# v1.net
KiCad netlist of a schematic drawn in EAGLE
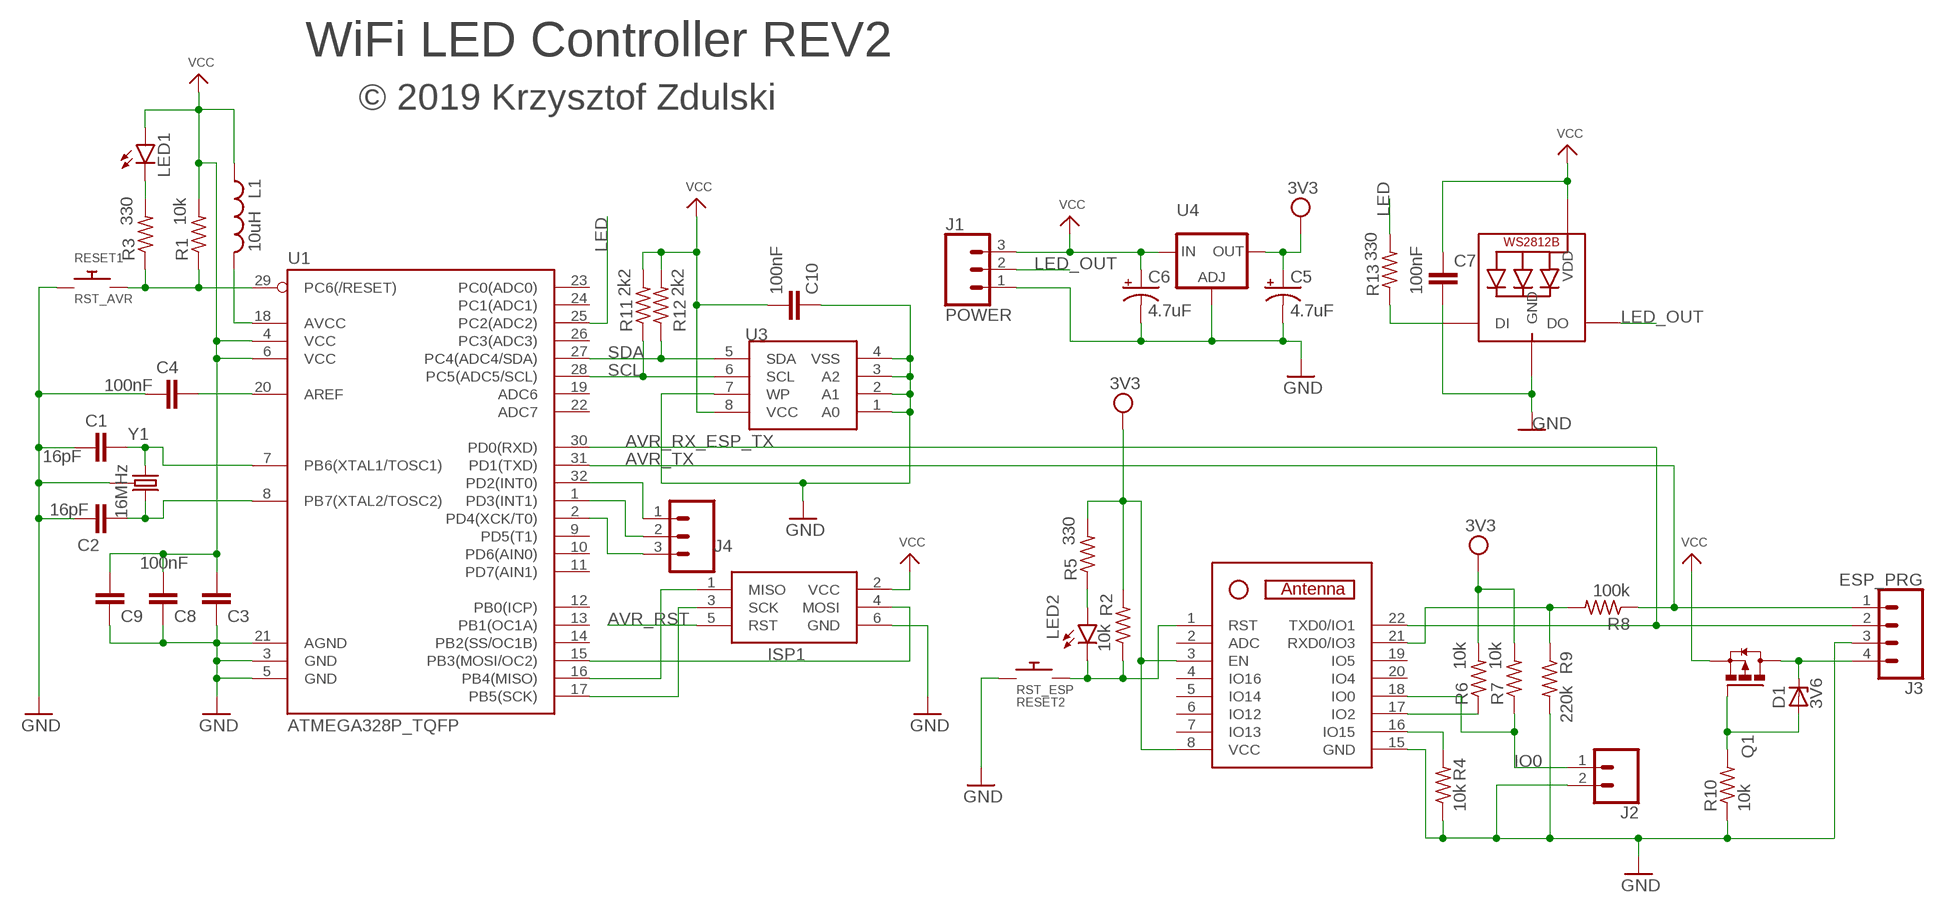
[diagram p0: schematic, sheet 1]

(export (version "E")
  (design (tool "Eeschema 10.0.6"))
  (components
    (comp (ref "C1")
      (value "16pF")
      (footprint "eagle-import:C0603K")
      (libsource (lib "eagle-import") (part "C-EUC0603K"))
    )
    (comp (ref "C2")
      (value "16pF")
      (footprint "eagle-import:C0603K")
      (libsource (lib "eagle-import") (part "C-EUC0603K"))
    )
    (comp (ref "C3")
      (value "100nF")
      (footprint "eagle-import:C0603")
      (libsource (lib "eagle-import") (part "C-EUC0603"))
    )
    (comp (ref "C4")
      (value "100nF")
      (footprint "eagle-import:C0603")
      (libsource (lib "eagle-import") (part "C-EUC0603"))
    )
    (comp (ref "C5")
      (value "4.7uF")
      (footprint "eagle-import:153CLV-0405")
      (libsource (lib "eagle-import") (part "CPOL-US153CLV-0405"))
    )
    (comp (ref "C6")
      (value "4.7uF")
      (footprint "eagle-import:153CLV-0405")
      (libsource (lib "eagle-import") (part "CPOL-US153CLV-0405"))
    )
    (comp (ref "C7")
      (value "100nF")
      (footprint "eagle-import:C0603")
      (libsource (lib "eagle-import") (part "C-EUC0603"))
    )
    (comp (ref "C8")
      (value "100nF")
      (footprint "eagle-import:C0603")
      (libsource (lib "eagle-import") (part "C-EUC0603"))
    )
    (comp (ref "C9")
      (value "100nF")
      (footprint "eagle-import:C0603")
      (libsource (lib "eagle-import") (part "C-EUC0603"))
    )
    (comp (ref "C10")
      (value "100nF")
      (footprint "eagle-import:C0603")
      (libsource (lib "eagle-import") (part "C-EUC0603"))
    )
    (comp (ref "D1")
      (value "3V6")
      (footprint "eagle-import:SOD123")
      (libsource (lib "eagle-import") (part "ZENNER_DIODE"))
    )
    (comp (ref "D2")
      (value "WS2812B")
      (footprint "eagle-import:WS2812B")
      (libsource (lib "eagle-import") (part "WS2812B"))
    )
    (comp (ref "ISP1")
      (value "AVRISP-6")
      (footprint "eagle-import:AVRISP")
      (libsource (lib "eagle-import") (part "AVRISP-6"))
    )
    (comp (ref "J1")
      (value "POWER")
      (footprint "eagle-import:MX-22-05-3031")
      (libsource (lib "eagle-import") (part "MX-22-05-3031"))
    )
    (comp (ref "J2")
      (value "CONN_02")
      (footprint "eagle-import:1X02")
      (libsource (lib "eagle-import") (part "CONN_02"))
    )
    (comp (ref "J3")
      (value "ESP_PRG")
      (footprint "eagle-import:1X04")
      (libsource (lib "eagle-import") (part "CONN_04"))
    )
    (comp (ref "J4")
      (value "CONN_03")
      (footprint "eagle-import:1X03")
      (libsource (lib "eagle-import") (part "CONN_03"))
    )
    (comp (ref "L1")
      (value "10uH")
      (footprint "eagle-import:L2012C")
      (libsource (lib "eagle-import") (part "L-USL2012C"))
    )
    (comp (ref "LED1")
      (value "LEDCHIP-LED0603")
      (footprint "eagle-import:CHIP-LED0603")
      (libsource (lib "eagle-import") (part "LEDCHIP-LED0603"))
    )
    (comp (ref "LED2")
      (value "LEDCHIP-LED0603")
      (footprint "eagle-import:CHIP-LED0603")
      (libsource (lib "eagle-import") (part "LEDCHIP-LED0603"))
    )
    (comp (ref "Q1")
      (value "FDN360P")
      (footprint "eagle-import:SUPER-SOT3")
      (libsource (lib "eagle-import") (part "FDN360P"))
    )
    (comp (ref "R1")
      (value "10k")
      (footprint "eagle-import:R0402")
      (libsource (lib "eagle-import") (part "R-US_R0402"))
    )
    (comp (ref "R2")
      (value "10k")
      (footprint "eagle-import:R0402")
      (libsource (lib "eagle-import") (part "R-US_R0402"))
    )
    (comp (ref "R3")
      (value "330")
      (footprint "eagle-import:R0603")
      (libsource (lib "eagle-import") (part "R-US_R0603"))
    )
    (comp (ref "R4")
      (value "10k")
      (footprint "eagle-import:R0603")
      (libsource (lib "eagle-import") (part "R-US_R0603"))
    )
    (comp (ref "R5")
      (value "330")
      (footprint "eagle-import:R0603")
      (libsource (lib "eagle-import") (part "R-US_R0603"))
    )
    (comp (ref "R6")
      (value "10k")
      (footprint "eagle-import:R0603")
      (libsource (lib "eagle-import") (part "R-US_R0603"))
    )
    (comp (ref "R7")
      (value "10k")
      (footprint "eagle-import:R0603")
      (libsource (lib "eagle-import") (part "R-US_R0603"))
    )
    (comp (ref "R8")
      (value "100k")
      (footprint "eagle-import:R0603")
      (libsource (lib "eagle-import") (part "R-US_R0603"))
    )
    (comp (ref "R9")
      (value "220k")
      (footprint "eagle-import:R0603")
      (libsource (lib "eagle-import") (part "R-US_R0603"))
    )
    (comp (ref "R10")
      (value "10k")
      (footprint "eagle-import:R0402")
      (libsource (lib "eagle-import") (part "R-US_R0402"))
    )
    (comp (ref "R11")
      (value "2k2")
      (footprint "eagle-import:R0603")
      (libsource (lib "eagle-import") (part "R-US_R0603"))
    )
    (comp (ref "R12")
      (value "2k2")
      (footprint "eagle-import:R0603")
      (libsource (lib "eagle-import") (part "R-US_R0603"))
    )
    (comp (ref "R13")
      (value "330")
      (footprint "eagle-import:R0603")
      (libsource (lib "eagle-import") (part "R-US_R0603"))
    )
    (comp (ref "RESET1")
      (value "RST_AVR")
      (footprint "eagle-import:TACTILE_SWITCH_SMD_6.2MM_TALL")
      (libsource (lib "eagle-import") (part "BUTTON"))
    )
    (comp (ref "RESET2")
      (value "RST_ESP")
      (footprint "eagle-import:TACTILE_SWITCH_SMD_6.2MM_TALL")
      (libsource (lib "eagle-import") (part "BUTTON"))
    )
    (comp (ref "U1")
      (value "ATMEGA328P_TQFP")
      (footprint "eagle-import:TQFP32-08")
      (libsource (lib "eagle-import") (part "ATMEGA328P_TQFP"))
    )
    (comp (ref "U2")
      (value "ESP-07")
      (footprint "eagle-import:ESP-07")
      (libsource (lib "eagle-import") (part "ESP-07"))
    )
    (comp (ref "U3")
      (value "EEPROM-I2CTSSOP8")
      (footprint "eagle-import:TSSOP8")
      (libsource (lib "eagle-import") (part "EEPROM-I2CTSSOP8"))
    )
    (comp (ref "U4")
      (value "LD117AS12TR")
      (footprint "eagle-import:SOT223")
      (libsource (lib "eagle-import") (part "LD117A?S12TR"))
    )
    (comp (ref "Y1")
      (value "16MHz")
      (footprint "eagle-import:CRYSTAL-SMD-3.2X2.5MM")
      (libsource (lib "eagle-import") (part "CRYSTAL"))
    )
  )
  (nets
    (net (code "1") (name "/AVR_RST") (class "Default")
      (node (ref "ISP1") (pin "5") (pinfunction "RST_5") (pintype "output"))
      (node (ref "R1") (pin "1") (pinfunction "1_1") (pintype "passive"))
      (node (ref "R3") (pin "1") (pinfunction "1_1") (pintype "passive"))
      (node (ref "RESET1") (pin "B1") (pinfunction "P$2_B1") (pintype "passive"))
      (node (ref "RESET1") (pin "B2") (pinfunction "P$2_B2") (pintype "passive"))
      (node (ref "U1") (pin "29") (pinfunction "PC6(/RESET)_29") (pintype "bidirectional"))
    )
    (net (code "2") (name "/AVR_RX_ESP_TX") (class "Default")
      (node (ref "J3") (pin "2") (pinfunction "2_2") (pintype "passive"))
      (node (ref "U1") (pin "30") (pinfunction "PD0(RXD)_30") (pintype "bidirectional"))
      (node (ref "U2") (pin "22") (pinfunction "TXD0/IO1_22") (pintype "bidirectional"))
    )
    (net (code "3") (name "/AVR_TX") (class "Default")
      (node (ref "J3") (pin "1") (pinfunction "1_1") (pintype "passive"))
      (node (ref "R8") (pin "1") (pinfunction "1_1") (pintype "passive"))
      (node (ref "U1") (pin "31") (pinfunction "PD1(TXD)_31") (pintype "bidirectional"))
    )
    (net (code "4") (name "/IO0") (class "Default")
      (node (ref "J2") (pin "1") (pinfunction "1_1") (pintype "passive"))
      (node (ref "R7") (pin "1") (pinfunction "1_1") (pintype "passive"))
      (node (ref "U2") (pin "18") (pinfunction "IO0_18") (pintype "bidirectional"))
    )
    (net (code "5") (name "/LED") (class "Default")
      (node (ref "R13") (pin "2") (pinfunction "2_2") (pintype "passive"))
      (node (ref "U1") (pin "25") (pinfunction "PC2(ADC2)_25") (pintype "bidirectional"))
    )
    (net (code "6") (name "/LED_OUT") (class "Default")
      (node (ref "D2") (pin "2-DOUT") (pinfunction "DO_2-DOUT") (pintype "output"))
      (node (ref "J1") (pin "2") (pinfunction "2_2") (pintype "passive"))
    )
    (net (code "7") (name "/SCL") (class "Default")
      (node (ref "R11") (pin "1") (pinfunction "1_1") (pintype "passive"))
      (node (ref "U1") (pin "28") (pinfunction "PC5(ADC5/SCL)_28") (pintype "bidirectional"))
      (node (ref "U3") (pin "6") (pinfunction "SCL_6") (pintype "bidirectional"))
    )
    (net (code "8") (name "/SDA") (class "Default")
      (node (ref "R12") (pin "1") (pinfunction "1_1") (pintype "passive"))
      (node (ref "U1") (pin "27") (pinfunction "PC4(ADC4/SDA)_27") (pintype "bidirectional"))
      (node (ref "U3") (pin "5") (pinfunction "SDA_5") (pintype "bidirectional"))
    )
    (net (code "9") (name "3V3") (class "Default")
      (node (ref "C5") (pin "+") (pinfunction "+_+") (pintype "passive"))
      (node (ref "R2") (pin "2") (pinfunction "2_2") (pintype "passive"))
      (node (ref "R5") (pin "2") (pinfunction "2_2") (pintype "passive"))
      (node (ref "R6") (pin "2") (pinfunction "2_2") (pintype "passive"))
      (node (ref "R7") (pin "2") (pinfunction "2_2") (pintype "passive"))
      (node (ref "U2") (pin "3") (pinfunction "EN_3") (pintype "bidirectional"))
      (node (ref "U2") (pin "8") (pinfunction "VCC_8") (pintype "bidirectional"))
      (node (ref "U4") (pin "4") (pinfunction "OUT_4") (pintype "passive"))
    )
    (net (code "10") (name "GND") (class "Default")
      (node (ref "C1") (pin "2") (pinfunction "2_2") (pintype "passive"))
      (node (ref "C10") (pin "2") (pinfunction "2_2") (pintype "passive"))
      (node (ref "C2") (pin "2") (pinfunction "2_2") (pintype "passive"))
      (node (ref "C3") (pin "2") (pinfunction "2_2") (pintype "passive"))
      (node (ref "C4") (pin "1") (pinfunction "1_1") (pintype "passive"))
      (node (ref "C5") (pin "-") (pinfunction "-_-") (pintype "passive"))
      (node (ref "C6") (pin "-") (pinfunction "-_-") (pintype "passive"))
      (node (ref "C7") (pin "2") (pinfunction "2_2") (pintype "passive"))
      (node (ref "C8") (pin "2") (pinfunction "2_2") (pintype "passive"))
      (node (ref "C9") (pin "2") (pinfunction "2_2") (pintype "passive"))
      (node (ref "D2") (pin "3-GND") (pinfunction "GND_3-GND") (pintype "power_in"))
      (node (ref "ISP1") (pin "6") (pinfunction "GND_6") (pintype "power_in"))
      (node (ref "J1") (pin "1") (pinfunction "1_1") (pintype "passive"))
      (node (ref "J2") (pin "2") (pinfunction "2_2") (pintype "passive"))
      (node (ref "J3") (pin "3") (pinfunction "3_3") (pintype "passive"))
      (node (ref "R10") (pin "1") (pinfunction "1_1") (pintype "passive"))
      (node (ref "R4") (pin "1") (pinfunction "1_1") (pintype "passive"))
      (node (ref "R9") (pin "2") (pinfunction "2_2") (pintype "passive"))
      (node (ref "RESET1") (pin "A1") (pinfunction "P$1_A1") (pintype "passive"))
      (node (ref "RESET1") (pin "A2") (pinfunction "P$1_A2") (pintype "passive"))
      (node (ref "RESET2") (pin "A1") (pinfunction "P$1_A1") (pintype "passive"))
      (node (ref "RESET2") (pin "A2") (pinfunction "P$1_A2") (pintype "passive"))
      (node (ref "U1") (pin "21") (pinfunction "AGND_21") (pintype "bidirectional"))
      (node (ref "U1") (pin "3") (pinfunction "GND_3") (pintype "bidirectional"))
      (node (ref "U1") (pin "5") (pinfunction "GND_5") (pintype "bidirectional"))
      (node (ref "U2") (pin "15") (pinfunction "GND_15") (pintype "bidirectional"))
      (node (ref "U3") (pin "1") (pinfunction "A0_1") (pintype "bidirectional"))
      (node (ref "U3") (pin "2") (pinfunction "A1_2") (pintype "bidirectional"))
      (node (ref "U3") (pin "3") (pinfunction "A2_3") (pintype "bidirectional"))
      (node (ref "U3") (pin "4") (pinfunction "VSS_4") (pintype "power_in"))
      (node (ref "U3") (pin "7") (pinfunction "WP_7") (pintype "bidirectional"))
      (node (ref "U4") (pin "1") (pinfunction "ADJ_1") (pintype "input"))
      (node (ref "Y1") (pin "2") (pinfunction "3_2") (pintype "passive"))
      (node (ref "Y1") (pin "4") (pinfunction "3_4") (pintype "passive"))
    )
    (net (code "11") (name "Net-(D2-DI)") (class "Default")
      (node (ref "D2") (pin "4-DIN") (pinfunction "DI_4-DIN") (pintype "input"))
      (node (ref "R13") (pin "1") (pinfunction "1_1") (pintype "passive"))
    )
    (net (code "12") (name "Net-(ISP1-MISO)") (class "Default")
      (node (ref "ISP1") (pin "1") (pinfunction "MISO_1") (pintype "input"))
      (node (ref "U1") (pin "16") (pinfunction "PB4(MISO)_16") (pintype "bidirectional"))
    )
    (net (code "13") (name "Net-(ISP1-MOSI)") (class "Default")
      (node (ref "ISP1") (pin "4") (pinfunction "MOSI_4") (pintype "output"))
      (node (ref "U1") (pin "15") (pinfunction "PB3(MOSI/OC2)_15") (pintype "bidirectional"))
    )
    (net (code "14") (name "Net-(ISP1-SCK)") (class "Default")
      (node (ref "ISP1") (pin "3") (pinfunction "SCK_3") (pintype "output"))
      (node (ref "U1") (pin "17") (pinfunction "PB5(SCK)_17") (pintype "bidirectional"))
    )
    (net (code "15") (name "Net-(LED1-PadC)") (class "Default")
      (node (ref "LED1") (pin "C") (pinfunction "C_C") (pintype "passive"))
      (node (ref "R3") (pin "2") (pinfunction "2_2") (pintype "passive"))
    )
    (net (code "16") (name "Net-(LED2-PadA)") (class "Default")
      (node (ref "LED2") (pin "A") (pinfunction "A_A") (pintype "passive"))
      (node (ref "R5") (pin "1") (pinfunction "1_1") (pintype "passive"))
    )
    (net (code "17") (name "Net-(Q1-D)") (class "Default")
      (node (ref "D1") (pin "C") (pinfunction "C_C") (pintype "passive"))
      (node (ref "J3") (pin "4") (pinfunction "4_4") (pintype "passive"))
      (node (ref "Q1") (pin "3") (pinfunction "D_3") (pintype "passive"))
    )
    (net (code "18") (name "Net-(Q1-G)") (class "Default")
      (node (ref "D1") (pin "A") (pinfunction "A_A") (pintype "passive"))
      (node (ref "Q1") (pin "1") (pinfunction "G_1") (pintype "passive"))
      (node (ref "R10") (pin "2") (pinfunction "2_2") (pintype "passive"))
    )
    (net (code "19") (name "Net-(U1-AREF)") (class "Default")
      (node (ref "C4") (pin "2") (pinfunction "2_2") (pintype "passive"))
      (node (ref "U1") (pin "20") (pinfunction "AREF_20") (pintype "bidirectional"))
    )
    (net (code "20") (name "Net-(U1-AVCC)") (class "Default")
      (node (ref "L1") (pin "2") (pinfunction "2_2") (pintype "passive"))
      (node (ref "U1") (pin "18") (pinfunction "AVCC_18") (pintype "bidirectional"))
    )
    (net (code "21") (name "Net-(U1-PB6(XTAL1{slash}TOSC1))") (class "Default")
      (node (ref "C1") (pin "1") (pinfunction "1_1") (pintype "passive"))
      (node (ref "U1") (pin "7") (pinfunction "PB6(XTAL1/TOSC1)_7") (pintype "bidirectional"))
      (node (ref "Y1") (pin "1") (pinfunction "1_1") (pintype "passive"))
    )
    (net (code "22") (name "Net-(U1-PB7(XTAL2{slash}TOSC2))") (class "Default")
      (node (ref "C2") (pin "1") (pinfunction "1_1") (pintype "passive"))
      (node (ref "U1") (pin "8") (pinfunction "PB7(XTAL2/TOSC2)_8") (pintype "bidirectional"))
      (node (ref "Y1") (pin "3") (pinfunction "2_3") (pintype "passive"))
    )
    (net (code "23") (name "Net-(U1-PD2(INT0))") (class "Default")
      (node (ref "J4") (pin "1") (pinfunction "1_1") (pintype "passive"))
      (node (ref "U1") (pin "32") (pinfunction "PD2(INT0)_32") (pintype "bidirectional"))
    )
    (net (code "24") (name "Net-(U1-PD3(INT1))") (class "Default")
      (node (ref "J4") (pin "2") (pinfunction "2_2") (pintype "passive"))
      (node (ref "U1") (pin "1") (pinfunction "PD3(INT1)_1") (pintype "bidirectional"))
    )
    (net (code "25") (name "Net-(U1-PD4(XCK{slash}T0))") (class "Default")
      (node (ref "J4") (pin "3") (pinfunction "3_3") (pintype "passive"))
      (node (ref "U1") (pin "2") (pinfunction "PD4(XCK/T0)_2") (pintype "bidirectional"))
    )
    (net (code "26") (name "Net-(U2-IO2)") (class "Default")
      (node (ref "R6") (pin "1") (pinfunction "1_1") (pintype "passive"))
      (node (ref "U2") (pin "17") (pinfunction "IO2_17") (pintype "bidirectional"))
    )
    (net (code "27") (name "Net-(U2-IO15)") (class "Default")
      (node (ref "R4") (pin "2") (pinfunction "2_2") (pintype "passive"))
      (node (ref "U2") (pin "16") (pinfunction "IO15_16") (pintype "bidirectional"))
    )
    (net (code "28") (name "Net-(U2-RST)") (class "Default")
      (node (ref "LED2") (pin "C") (pinfunction "C_C") (pintype "passive"))
      (node (ref "R2") (pin "1") (pinfunction "1_1") (pintype "passive"))
      (node (ref "RESET2") (pin "B1") (pinfunction "P$2_B1") (pintype "passive"))
      (node (ref "RESET2") (pin "B2") (pinfunction "P$2_B2") (pintype "passive"))
      (node (ref "U2") (pin "1") (pinfunction "RST_1") (pintype "bidirectional"))
    )
    (net (code "29") (name "Net-(U2-RXD0{slash}IO3)") (class "Default")
      (node (ref "R8") (pin "2") (pinfunction "2_2") (pintype "passive"))
      (node (ref "R9") (pin "1") (pinfunction "1_1") (pintype "passive"))
      (node (ref "U2") (pin "21") (pinfunction "RXD0/IO3_21") (pintype "bidirectional"))
    )
    (net (code "30") (name "VCC") (class "Default")
      (node (ref "C10") (pin "1") (pinfunction "1_1") (pintype "passive"))
      (node (ref "C3") (pin "1") (pinfunction "1_1") (pintype "passive"))
      (node (ref "C6") (pin "+") (pinfunction "+_+") (pintype "passive"))
      (node (ref "C7") (pin "1") (pinfunction "1_1") (pintype "passive"))
      (node (ref "C8") (pin "1") (pinfunction "1_1") (pintype "passive"))
      (node (ref "C9") (pin "1") (pinfunction "1_1") (pintype "passive"))
      (node (ref "D2") (pin "1-VDD") (pinfunction "VDD_1-VDD") (pintype "power_in"))
      (node (ref "ISP1") (pin "2") (pinfunction "VCC_2") (pintype "power_in"))
      (node (ref "J1") (pin "3") (pinfunction "3_3") (pintype "passive"))
      (node (ref "L1") (pin "1") (pinfunction "1_1") (pintype "passive"))
      (node (ref "LED1") (pin "A") (pinfunction "A_A") (pintype "passive"))
      (node (ref "Q1") (pin "2") (pinfunction "S_2") (pintype "passive"))
      (node (ref "R1") (pin "2") (pinfunction "2_2") (pintype "passive"))
      (node (ref "R11") (pin "2") (pinfunction "2_2") (pintype "passive"))
      (node (ref "R12") (pin "2") (pinfunction "2_2") (pintype "passive"))
      (node (ref "U1") (pin "4") (pinfunction "VCC_4") (pintype "bidirectional"))
      (node (ref "U1") (pin "6") (pinfunction "VCC_6") (pintype "bidirectional"))
      (node (ref "U3") (pin "8") (pinfunction "VCC_8") (pintype "power_in"))
      (node (ref "U4") (pin "3") (pinfunction "IN_3") (pintype "input"))
    )
    (net (code "31") (name "unconnected-(U1-ADC6-Pad19)") (class "Default")
      (node (ref "U1") (pin "19") (pinfunction "ADC6_19") (pintype "bidirectional"))
    )
    (net (code "32") (name "unconnected-(U1-ADC7-Pad22)") (class "Default")
      (node (ref "U1") (pin "22") (pinfunction "ADC7_22") (pintype "bidirectional"))
    )
    (net (code "33") (name "unconnected-(U1-PB0(ICP)-Pad12)") (class "Default")
      (node (ref "U1") (pin "12") (pinfunction "PB0(ICP)_12") (pintype "bidirectional"))
    )
    (net (code "34") (name "unconnected-(U1-PB1(OC1A)-Pad13)") (class "Default")
      (node (ref "U1") (pin "13") (pinfunction "PB1(OC1A)_13") (pintype "bidirectional"))
    )
    (net (code "35") (name "unconnected-(U1-PB2(SS{slash}OC1B)-Pad14)") (class "Default")
      (node (ref "U1") (pin "14") (pinfunction "PB2(SS/OC1B)_14") (pintype "bidirectional"))
    )
    (net (code "36") (name "unconnected-(U1-PC0(ADC0)-Pad23)") (class "Default")
      (node (ref "U1") (pin "23") (pinfunction "PC0(ADC0)_23") (pintype "bidirectional"))
    )
    (net (code "37") (name "unconnected-(U1-PC1(ADC1)-Pad24)") (class "Default")
      (node (ref "U1") (pin "24") (pinfunction "PC1(ADC1)_24") (pintype "bidirectional"))
    )
    (net (code "38") (name "unconnected-(U1-PC3(ADC3)-Pad26)") (class "Default")
      (node (ref "U1") (pin "26") (pinfunction "PC3(ADC3)_26") (pintype "bidirectional"))
    )
    (net (code "39") (name "unconnected-(U1-PD5(T1)-Pad9)") (class "Default")
      (node (ref "U1") (pin "9") (pinfunction "PD5(T1)_9") (pintype "bidirectional"))
    )
    (net (code "40") (name "unconnected-(U1-PD6(AIN0)-Pad10)") (class "Default")
      (node (ref "U1") (pin "10") (pinfunction "PD6(AIN0)_10") (pintype "bidirectional"))
    )
    (net (code "41") (name "unconnected-(U1-PD7(AIN1)-Pad11)") (class "Default")
      (node (ref "U1") (pin "11") (pinfunction "PD7(AIN1)_11") (pintype "bidirectional"))
    )
    (net (code "42") (name "unconnected-(U2-ADC-Pad2)") (class "Default")
      (node (ref "U2") (pin "2") (pinfunction "ADC_2") (pintype "bidirectional"))
    )
    (net (code "43") (name "unconnected-(U2-IO4-Pad20)") (class "Default")
      (node (ref "U2") (pin "20") (pinfunction "IO4_20") (pintype "bidirectional"))
    )
    (net (code "44") (name "unconnected-(U2-IO5-Pad19)") (class "Default")
      (node (ref "U2") (pin "19") (pinfunction "IO5_19") (pintype "bidirectional"))
    )
    (net (code "45") (name "unconnected-(U2-IO12-Pad6)") (class "Default")
      (node (ref "U2") (pin "6") (pinfunction "IO12_6") (pintype "bidirectional"))
    )
    (net (code "46") (name "unconnected-(U2-IO13-Pad7)") (class "Default")
      (node (ref "U2") (pin "7") (pinfunction "IO13_7") (pintype "bidirectional"))
    )
    (net (code "47") (name "unconnected-(U2-IO14-Pad5)") (class "Default")
      (node (ref "U2") (pin "5") (pinfunction "IO14_5") (pintype "bidirectional"))
    )
    (net (code "48") (name "unconnected-(U2-IO16-Pad4)") (class "Default")
      (node (ref "U2") (pin "4") (pinfunction "IO16_4") (pintype "bidirectional"))
    )
  )
)
